# AD_i2C_SPI.net
KiCad netlist of a schematic drawn in Altium Designer
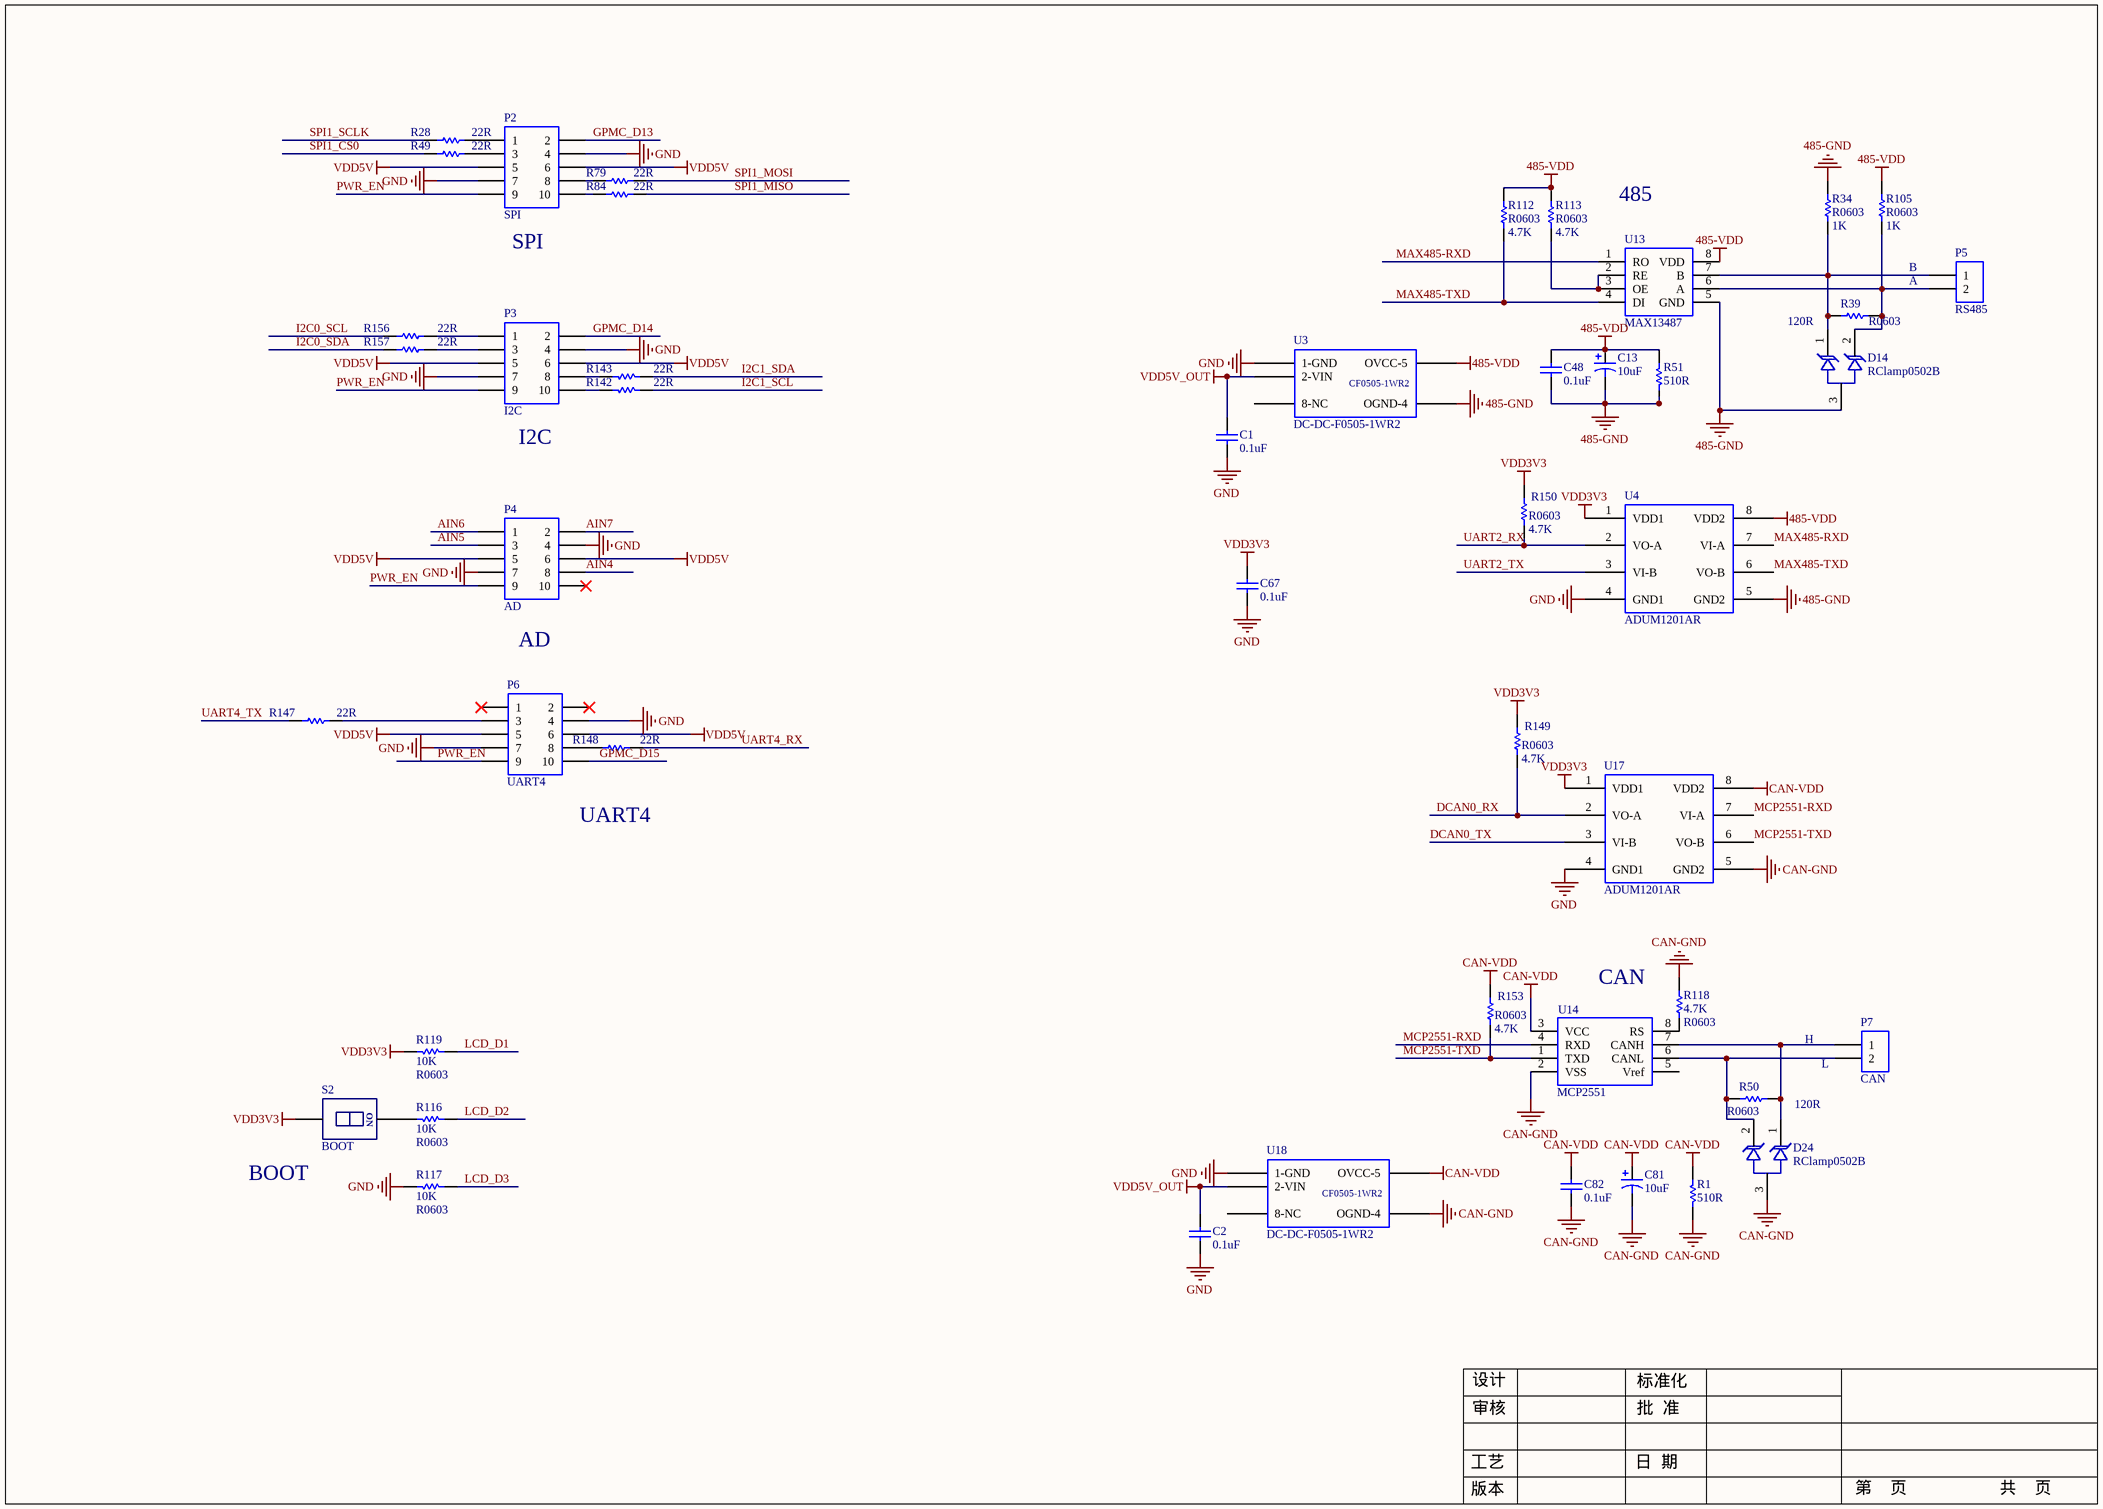
[diagram p0: AD & i2C & SPI.SchDoc]

(export (version "E")
  (design (tool "Eeschema 10.0.6"))
  (components
    (comp (ref "C1")
      (value "0.1uF")
      (description "Capacitor")
      (fields (field (name "Comment") "C0603") (field (name "PUBLISHER") "Altium Limited"))
      (libsource (lib "OK335xD") (part "Cap"))
    )
    (comp (ref "C2")
      (value "0.1uF")
      (description "Capacitor")
      (fields (field (name "Comment") "C0603") (field (name "PUBLISHER") "Altium Limited"))
      (libsource (lib "OK335xD") (part "Cap"))
    )
    (comp (ref "C13")
      (value "10uF")
      (footprint "TC3216A")
      (description "Polarized Capacitor (Surface Mount)")
      (fields (field (name "Comment") "Cap Pol3") (field (name "PUBLISHER") "Altium Limited"))
      (libsource (lib "OK335xD") (part "Cap Pol3"))
    )
    (comp (ref "C48")
      (value "0.1uF")
      (description "Capacitor")
      (fields (field (name "Comment") "C0603") (field (name "PUBLISHER") "Altium Limited"))
      (libsource (lib "OK335xD") (part "Cap"))
    )
    (comp (ref "C67")
      (value "0.1uF")
      (description "Capacitor")
      (fields (field (name "Comment") "C0603") (field (name "PUBLISHER") "Altium Limited"))
      (libsource (lib "OK335xD") (part "Cap"))
    )
    (comp (ref "C81")
      (value "10uF")
      (footprint "TC3216A")
      (description "Polarized Capacitor (Surface Mount)")
      (fields (field (name "Comment") "Cap Pol3") (field (name "PUBLISHER") "Altium Limited"))
      (libsource (lib "OK335xD") (part "Cap Pol3"))
    )
    (comp (ref "C82")
      (value "0.1uF")
      (description "Capacitor")
      (fields (field (name "Comment") "C0603") (field (name "PUBLISHER") "Altium Limited"))
      (libsource (lib "OK335xD") (part "Cap"))
    )
    (comp (ref "D14")
      (value "RClamp0502B")
      (footprint "SOT-523")
      (fields (field (name "Comment") "LCTVS"))
      (libsource (lib "Sch") (part "LCTVS"))
    )
    (comp (ref "D24")
      (value "RClamp0502B")
      (footprint "SOT-523")
      (fields (field (name "Comment") "LCTVS"))
      (libsource (lib "Sch") (part "LCTVS"))
    )
    (comp (ref "P2")
      (value "SPI")
      (footprint "IDC10S")
      (description "Header, 5-Pin, Dual row")
      (fields (field (name "PUBLISHER") "Altium Limited"))
      (libsource (lib "OK335xD") (part "Header 5X2"))
    )
    (comp (ref "P3")
      (value "I2C")
      (footprint "IDC10S")
      (description "Header, 5-Pin, Dual row")
      (fields (field (name "PUBLISHER") "Altium Limited"))
      (libsource (lib "OK335xD") (part "Header 5X2"))
    )
    (comp (ref "P4")
      (value "AD")
      (footprint "IDC10S")
      (description "Header, 5-Pin, Dual row")
      (fields (field (name "PUBLISHER") "Altium Limited"))
      (libsource (lib "OK335xD") (part "Header 5X2"))
    )
    (comp (ref "P5")
      (value "RS485")
      (footprint "2EDGKA-5.08-2P")
      (description "Header, 2-Pin")
      (fields (field (name "PUBLISHER") "Altium Limited"))
      (libsource (lib "OK335xD") (part "Header 2"))
    )
    (comp (ref "P6")
      (value "UART4")
      (footprint "IDC10S")
      (description "Header, 5-Pin, Dual row")
      (fields (field (name "PUBLISHER") "Altium Limited"))
      (libsource (lib "OK335xD") (part "Header 5X2"))
    )
    (comp (ref "P7")
      (value "CAN")
      (footprint "2EDGKA-5.08-2P")
      (description "Header, 2-Pin")
      (fields (field (name "PUBLISHER") "Altium Limited"))
      (libsource (lib "OK335xD") (part "Header 2"))
    )
    (comp (ref "R1")
      (value "510R")
      (footprint "1206")
      (description "Resistor")
      (fields (field (name "Comment") "R1808") (field (name "PUBLISHER") "Altium Limited"))
      (libsource (lib "Miscellaneous Devices") (part "Res1"))
    )
    (comp (ref "R28")
      (value "22R")
      (footprint "OK335xD_V1.0:R0603_M1608")
      (description "Resistor")
      (fields (field (name "Comment") "R0603") (field (name "PUBLISHER") "Altium Limited"))
      (libsource (lib "Miscellaneous Devices") (part "Res1"))
    )
    (comp (ref "R34")
      (value "R0603")
      (footprint "OK335xD_V1.0:R0603_M1608")
      (description "Resistor")
      (fields (field (name "ALTIUM_VALUE") "1K") (field (name "PUBLISHER") "Altium Limited"))
      (libsource (lib "Miscellaneous Devices") (part "Res1"))
    )
    (comp (ref "R39")
      (value "R0603")
      (footprint "OK335xD_V1.0:R0603_M1608")
      (description "Resistor")
      (fields (field (name "ALTIUM_VALUE") "120R") (field (name "PUBLISHER") "Altium Limited"))
      (libsource (lib "Miscellaneous Devices") (part "Res1"))
    )
    (comp (ref "R49")
      (value "22R")
      (footprint "OK335xD_V1.0:R0603_M1608")
      (description "Resistor")
      (fields (field (name "Comment") "R0603") (field (name "PUBLISHER") "Altium Limited"))
      (libsource (lib "Miscellaneous Devices") (part "Res1"))
    )
    (comp (ref "R50")
      (value "R0603")
      (footprint "OK335xD_V1.0:R0603_M1608")
      (description "Resistor")
      (fields (field (name "ALTIUM_VALUE") "120R") (field (name "PUBLISHER") "Altium Limited"))
      (libsource (lib "Miscellaneous Devices") (part "Res1"))
    )
    (comp (ref "R51")
      (value "510R")
      (footprint "1206")
      (description "Resistor")
      (fields (field (name "Comment") "R1808") (field (name "PUBLISHER") "Altium Limited"))
      (libsource (lib "Miscellaneous Devices") (part "Res1"))
    )
    (comp (ref "R79")
      (value "22R")
      (footprint "OK335xD_V1.0:R0603_M1608")
      (description "Resistor")
      (fields (field (name "Comment") "R0603") (field (name "PUBLISHER") "Altium Limited"))
      (libsource (lib "Miscellaneous Devices") (part "Res1"))
    )
    (comp (ref "R84")
      (value "22R")
      (footprint "OK335xD_V1.0:R0603_M1608")
      (description "Resistor")
      (fields (field (name "Comment") "R0603") (field (name "PUBLISHER") "Altium Limited"))
      (libsource (lib "Miscellaneous Devices") (part "Res1"))
    )
    (comp (ref "R105")
      (value "R0603")
      (footprint "OK335xD_V1.0:R0603_M1608")
      (description "Resistor")
      (fields (field (name "ALTIUM_VALUE") "1K") (field (name "PUBLISHER") "Altium Limited"))
      (libsource (lib "Miscellaneous Devices") (part "Res1"))
    )
    (comp (ref "R112")
      (value "R0603")
      (footprint "OK335xD_V1.0:R0603_M1608")
      (description "Resistor")
      (fields (field (name "ALTIUM_VALUE") "4.7K") (field (name "PUBLISHER") "Altium Limited"))
      (libsource (lib "Miscellaneous Devices") (part "Res1"))
    )
    (comp (ref "R113")
      (value "R0603")
      (footprint "OK335xD_V1.0:R0603_M1608")
      (description "Resistor")
      (fields (field (name "ALTIUM_VALUE") "4.7K") (field (name "PUBLISHER") "Altium Limited"))
      (libsource (lib "Miscellaneous Devices") (part "Res1"))
    )
    (comp (ref "R116")
      (value "10K")
      (footprint "R0603_M1608")
      (description "R0603")
      (fields (field (name "ALTIUM_VALUE") "R0603") (field (name "PUBLISHER") "Altium Limited"))
      (libsource (lib "Miscellaneous Devices") (part "Res1"))
    )
    (comp (ref "R117")
      (value "10K")
      (footprint "R0603_M1608")
      (description "R0603")
      (fields (field (name "ALTIUM_VALUE") "R0603") (field (name "PUBLISHER") "Altium Limited"))
      (libsource (lib "Miscellaneous Devices") (part "Res1"))
    )
    (comp (ref "R118")
      (value "4.7K")
      (footprint "R0603_M1608")
      (description "R0603")
      (fields (field (name "ALTIUM_VALUE") "R0603") (field (name "PUBLISHER") "Altium Limited"))
      (libsource (lib "Miscellaneous Devices") (part "Res1"))
    )
    (comp (ref "R119")
      (value "10K")
      (footprint "R0603_M1608")
      (description "R0603")
      (fields (field (name "ALTIUM_VALUE") "R0603") (field (name "PUBLISHER") "Altium Limited"))
      (libsource (lib "Miscellaneous Devices") (part "Res1"))
    )
    (comp (ref "R142")
      (value "22R")
      (footprint "OK335xD_V1.0:R0603_M1608")
      (description "Resistor")
      (fields (field (name "Comment") "R0603") (field (name "PUBLISHER") "Altium Limited"))
      (libsource (lib "Miscellaneous Devices") (part "Res1"))
    )
    (comp (ref "R143")
      (value "22R")
      (footprint "OK335xD_V1.0:R0603_M1608")
      (description "Resistor")
      (fields (field (name "Comment") "R0603") (field (name "PUBLISHER") "Altium Limited"))
      (libsource (lib "Miscellaneous Devices") (part "Res1"))
    )
    (comp (ref "R147")
      (value "22R")
      (footprint "OK335xD_V1.0:R0603_M1608")
      (description "Resistor")
      (fields (field (name "Comment") "R0603") (field (name "PUBLISHER") "Altium Limited"))
      (libsource (lib "Miscellaneous Devices") (part "Res1"))
    )
    (comp (ref "R148")
      (value "22R")
      (footprint "OK335xD_V1.0:R0603_M1608")
      (description "Resistor")
      (fields (field (name "Comment") "R0603") (field (name "PUBLISHER") "Altium Limited"))
      (libsource (lib "Miscellaneous Devices") (part "Res1"))
    )
    (comp (ref "R149")
      (value "R0603")
      (footprint "OK335xD_V1.0:R0603_M1608")
      (description "Resistor")
      (fields (field (name "ALTIUM_VALUE") "4.7K") (field (name "PUBLISHER") "Altium Limited"))
      (libsource (lib "Miscellaneous Devices") (part "Res1"))
    )
    (comp (ref "R150")
      (value "R0603")
      (footprint "OK335xD_V1.0:R0603_M1608")
      (description "Resistor")
      (fields (field (name "ALTIUM_VALUE") "4.7K") (field (name "PUBLISHER") "Altium Limited"))
      (libsource (lib "Miscellaneous Devices") (part "Res1"))
    )
    (comp (ref "R153")
      (value "R0603")
      (footprint "OK335xD_V1.0:R0603_M1608")
      (description "Resistor")
      (fields (field (name "ALTIUM_VALUE") "4.7K") (field (name "PUBLISHER") "Altium Limited"))
      (libsource (lib "Miscellaneous Devices") (part "Res1"))
    )
    (comp (ref "R156")
      (value "22R")
      (footprint "OK335xD_V1.0:R0603_M1608")
      (description "Resistor")
      (fields (field (name "Comment") "R0603") (field (name "PUBLISHER") "Altium Limited"))
      (libsource (lib "Miscellaneous Devices") (part "Res1"))
    )
    (comp (ref "R157")
      (value "22R")
      (footprint "OK335xD_V1.0:R0603_M1608")
      (description "Resistor")
      (fields (field (name "Comment") "R0603") (field (name "PUBLISHER") "Altium Limited"))
      (libsource (lib "Miscellaneous Devices") (part "Res1"))
    )
    (comp (ref "S2")
      (value "BOOT")
      (footprint "SWITCH_1P")
      (libsource (lib "Miscellaneous Connectors") (part "SW DIP-1"))
    )
    (comp (ref "U3")
      (value "DC-DC-F0505-1WR2")
      (footprint "CF0505-1WR2")
      (libsource (lib "OK335xD") (part "DC-DC-F0505-1WR2"))
    )
    (comp (ref "U4")
      (value "ADUM1201AR")
      (footprint "SO8_N - ADUM1201")
      (libsource (lib "OK335xD") (part "ADuM1201"))
    )
    (comp (ref "U13")
      (value "MAX13487")
      (footprint "SOIC-8N")
      (description "SOIC8")
      (libsource (lib "OK335xD") (part "MAX485"))
    )
    (comp (ref "U14")
      (value "MCP2551")
      (footprint "SOIC-8N")
      (description "SOIC8")
      (libsource (lib "OK335xD") (part "MCP2551"))
    )
    (comp (ref "U17")
      (value "ADUM1201AR")
      (footprint "SO8_N - ADUM1201")
      (libsource (lib "OK335xD") (part "ADuM1201"))
    )
    (comp (ref "U18")
      (value "DC-DC-F0505-1WR2")
      (footprint "CF0505-1WR2")
      (libsource (lib "OK335xD") (part "DC-DC-F0505-1WR2"))
    )
  )
  (nets
    (net (code "1") (name "/AIN4") (class "Default")
      (node (ref "P4") (pin "8") (pinfunction "8_8") (pintype "passive"))
    )
    (net (code "2") (name "/AIN5") (class "Default")
      (node (ref "P4") (pin "3") (pinfunction "3_3") (pintype "passive"))
    )
    (net (code "3") (name "/AIN6") (class "Default")
      (node (ref "P4") (pin "1") (pinfunction "1_1") (pintype "passive"))
    )
    (net (code "4") (name "/AIN7") (class "Default")
      (node (ref "P4") (pin "2") (pinfunction "2_2") (pintype "passive"))
    )
    (net (code "5") (name "/DCAN0_RX") (class "Default")
      (node (ref "R149") (pin "2") (pinfunction "2_2") (pintype "passive"))
      (node (ref "U17") (pin "2") (pinfunction "VO-A_2") (pintype "passive"))
    )
    (net (code "6") (name "/DCAN0_TX") (class "Default")
      (node (ref "U17") (pin "3") (pinfunction "VI-B_3") (pintype "passive"))
    )
    (net (code "7") (name "/GPMC_D13") (class "Default")
      (node (ref "P2") (pin "2") (pinfunction "2_2") (pintype "passive"))
    )
    (net (code "8") (name "/GPMC_D14") (class "Default")
      (node (ref "P3") (pin "2") (pinfunction "2_2") (pintype "passive"))
    )
    (net (code "9") (name "/GPMC_D15") (class "Default")
      (node (ref "P6") (pin "10") (pinfunction "10_10") (pintype "passive"))
    )
    (net (code "10") (name "/I2C0_SCL") (class "Default")
      (node (ref "R156") (pin "2") (pinfunction "2_2") (pintype "passive"))
    )
    (net (code "11") (name "/I2C0_SDA") (class "Default")
      (node (ref "R157") (pin "2") (pinfunction "2_2") (pintype "passive"))
    )
    (net (code "12") (name "/I2C1_SCL") (class "Default")
      (node (ref "R142") (pin "1") (pinfunction "1_1") (pintype "passive"))
    )
    (net (code "13") (name "/I2C1_SDA") (class "Default")
      (node (ref "R143") (pin "1") (pinfunction "1_1") (pintype "passive"))
    )
    (net (code "14") (name "/LCD_D1") (class "Default")
      (node (ref "R119") (pin "1") (pinfunction "1_1") (pintype "passive"))
    )
    (net (code "15") (name "/LCD_D2") (class "Default")
      (node (ref "R116") (pin "1") (pinfunction "1_1") (pintype "passive"))
    )
    (net (code "16") (name "/LCD_D3") (class "Default")
      (node (ref "R117") (pin "1") (pinfunction "1_1") (pintype "passive"))
    )
    (net (code "17") (name "/MAX485-RXD") (class "Default")
      (node (ref "U13") (pin "1") (pinfunction "RO_1") (pintype "passive"))
      (node (ref "U4") (pin "7") (pinfunction "VI-A_7") (pintype "passive"))
    )
    (net (code "18") (name "/MAX485-TXD") (class "Default")
      (node (ref "R112") (pin "2") (pinfunction "2_2") (pintype "passive"))
      (node (ref "U13") (pin "4") (pinfunction "DI_4") (pintype "passive"))
      (node (ref "U4") (pin "6") (pinfunction "VO-B_6") (pintype "passive"))
    )
    (net (code "19") (name "/MCP2551-RXD") (class "Default")
      (node (ref "U14") (pin "4") (pinfunction "RXD_4") (pintype "passive"))
      (node (ref "U17") (pin "7") (pinfunction "VI-A_7") (pintype "passive"))
    )
    (net (code "20") (name "/MCP2551-TXD") (class "Default")
      (node (ref "R153") (pin "2") (pinfunction "2_2") (pintype "passive"))
      (node (ref "U14") (pin "1") (pinfunction "TXD_1") (pintype "passive"))
      (node (ref "U17") (pin "6") (pinfunction "VO-B_6") (pintype "passive"))
    )
    (net (code "21") (name "/PWR_EN") (class "Default")
      (node (ref "P2") (pin "9") (pinfunction "9_9") (pintype "passive"))
      (node (ref "P3") (pin "9") (pinfunction "9_9") (pintype "passive"))
      (node (ref "P4") (pin "9") (pinfunction "9_9") (pintype "passive"))
      (node (ref "P6") (pin "9") (pinfunction "9_9") (pintype "passive"))
    )
    (net (code "22") (name "/SPI1_CS0") (class "Default")
      (node (ref "R49") (pin "2") (pinfunction "2_2") (pintype "passive"))
    )
    (net (code "23") (name "/SPI1_MISO") (class "Default")
      (node (ref "R84") (pin "1") (pinfunction "1_1") (pintype "passive"))
    )
    (net (code "24") (name "/SPI1_MOSI") (class "Default")
      (node (ref "R79") (pin "1") (pinfunction "1_1") (pintype "passive"))
    )
    (net (code "25") (name "/SPI1_SCLK") (class "Default")
      (node (ref "R28") (pin "2") (pinfunction "2_2") (pintype "passive"))
    )
    (net (code "26") (name "/UART2_RX") (class "Default")
      (node (ref "R150") (pin "2") (pinfunction "2_2") (pintype "passive"))
      (node (ref "U4") (pin "2") (pinfunction "VO-A_2") (pintype "passive"))
    )
    (net (code "27") (name "/UART2_TX") (class "Default")
      (node (ref "U4") (pin "3") (pinfunction "VI-B_3") (pintype "passive"))
    )
    (net (code "28") (name "/UART4_RX") (class "Default")
      (node (ref "R148") (pin "2") (pinfunction "2_2") (pintype "passive"))
    )
    (net (code "29") (name "/UART4_TX") (class "Default")
      (node (ref "R147") (pin "1") (pinfunction "1_1") (pintype "passive"))
    )
    (net (code "30") (name "485-GND") (class "Default")
      (node (ref "C13") (pin "2") (pinfunction "2_2") (pintype "passive"))
      (node (ref "C48") (pin "1") (pinfunction "1_1") (pintype "passive"))
      (node (ref "D14") (pin "3") (pintype "passive"))
      (node (ref "R34") (pin "1") (pinfunction "1_1") (pintype "passive"))
      (node (ref "R51") (pin "2") (pinfunction "2_2") (pintype "passive"))
      (node (ref "U13") (pin "5") (pinfunction "GND_5") (pintype "passive"))
      (node (ref "U3") (pin "4") (pinfunction "OGND-4_4") (pintype "passive"))
      (node (ref "U4") (pin "5") (pinfunction "GND2_5") (pintype "passive"))
    )
    (net (code "31") (name "485-VDD") (class "Default")
      (node (ref "C13") (pin "1") (pinfunction "1_1") (pintype "passive"))
      (node (ref "C48") (pin "2") (pinfunction "2_2") (pintype "passive"))
      (node (ref "R105") (pin "1") (pinfunction "1_1") (pintype "passive"))
      (node (ref "R112") (pin "1") (pinfunction "1_1") (pintype "passive"))
      (node (ref "R113") (pin "1") (pinfunction "1_1") (pintype "passive"))
      (node (ref "R51") (pin "1") (pinfunction "1_1") (pintype "passive"))
      (node (ref "U13") (pin "8") (pinfunction "VDD_8") (pintype "passive"))
      (node (ref "U3") (pin "5") (pinfunction "OVCC-5_5") (pintype "passive"))
      (node (ref "U4") (pin "8") (pinfunction "VDD2_8") (pintype "passive"))
    )
    (net (code "32") (name "CAN-GND") (class "Default")
      (node (ref "C81") (pin "2") (pinfunction "2_2") (pintype "passive"))
      (node (ref "C82") (pin "1") (pinfunction "1_1") (pintype "passive"))
      (node (ref "D24") (pin "3") (pintype "passive"))
      (node (ref "R1") (pin "2") (pinfunction "2_2") (pintype "passive"))
      (node (ref "R118") (pin "1") (pinfunction "1_1") (pintype "passive"))
      (node (ref "U14") (pin "2") (pinfunction "VSS_2") (pintype "passive"))
      (node (ref "U17") (pin "5") (pinfunction "GND2_5") (pintype "passive"))
      (node (ref "U18") (pin "4") (pinfunction "OGND-4_4") (pintype "passive"))
    )
    (net (code "33") (name "CAN-VDD") (class "Default")
      (node (ref "C81") (pin "1") (pinfunction "1_1") (pintype "passive"))
      (node (ref "C82") (pin "2") (pinfunction "2_2") (pintype "passive"))
      (node (ref "R1") (pin "1") (pinfunction "1_1") (pintype "passive"))
      (node (ref "R153") (pin "1") (pinfunction "1_1") (pintype "passive"))
      (node (ref "U14") (pin "3") (pinfunction "VCC_3") (pintype "passive"))
      (node (ref "U17") (pin "8") (pinfunction "VDD2_8") (pintype "passive"))
      (node (ref "U18") (pin "5") (pinfunction "OVCC-5_5") (pintype "passive"))
    )
    (net (code "34") (name "GND") (class "Default")
      (node (ref "C1") (pin "1") (pinfunction "1_1") (pintype "passive"))
      (node (ref "C2") (pin "1") (pinfunction "1_1") (pintype "passive"))
      (node (ref "C67") (pin "1") (pinfunction "1_1") (pintype "passive"))
      (node (ref "P2") (pin "4") (pinfunction "4_4") (pintype "passive"))
      (node (ref "P2") (pin "7") (pinfunction "7_7") (pintype "passive"))
      (node (ref "P3") (pin "4") (pinfunction "4_4") (pintype "passive"))
      (node (ref "P3") (pin "7") (pinfunction "7_7") (pintype "passive"))
      (node (ref "P4") (pin "4") (pinfunction "4_4") (pintype "passive"))
      (node (ref "P4") (pin "7") (pinfunction "7_7") (pintype "passive"))
      (node (ref "P6") (pin "4") (pinfunction "4_4") (pintype "passive"))
      (node (ref "P6") (pin "7") (pinfunction "7_7") (pintype "passive"))
      (node (ref "R117") (pin "2") (pinfunction "2_2") (pintype "passive"))
      (node (ref "U17") (pin "4") (pinfunction "GND1_4") (pintype "passive"))
      (node (ref "U18") (pin "1") (pinfunction "1-GND_1") (pintype "passive"))
      (node (ref "U3") (pin "1") (pinfunction "1-GND_1") (pintype "passive"))
      (node (ref "U4") (pin "4") (pinfunction "GND1_4") (pintype "passive"))
    )
    (net (code "35") (name "Net-(P2-Pad1)") (class "Default")
      (node (ref "P2") (pin "1") (pinfunction "1_1") (pintype "passive"))
      (node (ref "R28") (pin "1") (pinfunction "1_1") (pintype "passive"))
    )
    (net (code "36") (name "Net-(P2-Pad3)") (class "Default")
      (node (ref "P2") (pin "3") (pinfunction "3_3") (pintype "passive"))
      (node (ref "R49") (pin "1") (pinfunction "1_1") (pintype "passive"))
    )
    (net (code "37") (name "Net-(P2-Pad8)") (class "Default")
      (node (ref "P2") (pin "8") (pinfunction "8_8") (pintype "passive"))
      (node (ref "R79") (pin "2") (pinfunction "2_2") (pintype "passive"))
    )
    (net (code "38") (name "Net-(P2-Pad10)") (class "Default")
      (node (ref "P2") (pin "10") (pinfunction "10_10") (pintype "passive"))
      (node (ref "R84") (pin "2") (pinfunction "2_2") (pintype "passive"))
    )
    (net (code "39") (name "Net-(P3-Pad1)") (class "Default")
      (node (ref "P3") (pin "1") (pinfunction "1_1") (pintype "passive"))
      (node (ref "R156") (pin "1") (pinfunction "1_1") (pintype "passive"))
    )
    (net (code "40") (name "Net-(P3-Pad3)") (class "Default")
      (node (ref "P3") (pin "3") (pinfunction "3_3") (pintype "passive"))
      (node (ref "R157") (pin "1") (pinfunction "1_1") (pintype "passive"))
    )
    (net (code "41") (name "Net-(P3-Pad8)") (class "Default")
      (node (ref "P3") (pin "8") (pinfunction "8_8") (pintype "passive"))
      (node (ref "R143") (pin "2") (pinfunction "2_2") (pintype "passive"))
    )
    (net (code "42") (name "Net-(P3-Pad10)") (class "Default")
      (node (ref "P3") (pin "10") (pinfunction "10_10") (pintype "passive"))
      (node (ref "R142") (pin "2") (pinfunction "2_2") (pintype "passive"))
    )
    (net (code "43") (name "Net-(P6-Pad3)") (class "Default")
      (node (ref "P6") (pin "3") (pinfunction "3_3") (pintype "passive"))
      (node (ref "R147") (pin "2") (pinfunction "2_2") (pintype "passive"))
    )
    (net (code "44") (name "Net-(P6-Pad8)") (class "Default")
      (node (ref "P6") (pin "8") (pinfunction "8_8") (pintype "passive"))
      (node (ref "R148") (pin "1") (pinfunction "1_1") (pintype "passive"))
    )
    (net (code "45") (name "Net-(R116-Pad2)") (class "Default")
      (node (ref "R116") (pin "2") (pinfunction "2_2") (pintype "passive"))
      (node (ref "S2") (pin "2") (pinfunction "2_2") (pintype "passive"))
    )
    (net (code "46") (name "Net-(U13-A)") (class "Default")
      (node (ref "D14") (pin "2") (pinfunction "2_2") (pintype "passive"))
      (node (ref "P5") (pin "2") (pinfunction "2_2") (pintype "passive"))
      (node (ref "R105") (pin "2") (pinfunction "2_2") (pintype "passive"))
      (node (ref "R39") (pin "1") (pinfunction "1_1") (pintype "passive"))
      (node (ref "U13") (pin "6") (pinfunction "A_6") (pintype "passive"))
    )
    (net (code "47") (name "Net-(U13-B)") (class "Default")
      (node (ref "D14") (pin "1") (pinfunction "1_1") (pintype "passive"))
      (node (ref "P5") (pin "1") (pinfunction "1_1") (pintype "passive"))
      (node (ref "R34") (pin "2") (pinfunction "2_2") (pintype "passive"))
      (node (ref "R39") (pin "2") (pinfunction "2_2") (pintype "passive"))
      (node (ref "U13") (pin "7") (pinfunction "B_7") (pintype "passive"))
    )
    (net (code "48") (name "Net-(U13-OE)") (class "Default")
      (node (ref "R113") (pin "2") (pinfunction "2_2") (pintype "passive"))
      (node (ref "U13") (pin "2") (pinfunction "RE_2") (pintype "passive"))
      (node (ref "U13") (pin "3") (pinfunction "OE_3") (pintype "passive"))
    )
    (net (code "49") (name "Net-(U14-CANH)") (class "Default")
      (node (ref "D24") (pin "1") (pinfunction "1_1") (pintype "passive"))
      (node (ref "P7") (pin "1") (pinfunction "1_1") (pintype "passive"))
      (node (ref "R50") (pin "1") (pinfunction "1_1") (pintype "passive"))
      (node (ref "U14") (pin "7") (pinfunction "CANH_7") (pintype "passive"))
    )
    (net (code "50") (name "Net-(U14-CANL)") (class "Default")
      (node (ref "D24") (pin "2") (pinfunction "2_2") (pintype "passive"))
      (node (ref "P7") (pin "2") (pinfunction "2_2") (pintype "passive"))
      (node (ref "R50") (pin "2") (pinfunction "2_2") (pintype "passive"))
      (node (ref "U14") (pin "6") (pinfunction "CANL_6") (pintype "passive"))
    )
    (net (code "51") (name "Net-(U14-RS)") (class "Default")
      (node (ref "R118") (pin "2") (pinfunction "2_2") (pintype "passive"))
      (node (ref "U14") (pin "8") (pinfunction "RS_8") (pintype "passive"))
    )
    (net (code "52") (name "VDD3V3") (class "Default")
      (node (ref "C67") (pin "2") (pinfunction "2_2") (pintype "passive"))
      (node (ref "R119") (pin "2") (pinfunction "2_2") (pintype "passive"))
      (node (ref "R149") (pin "1") (pinfunction "1_1") (pintype "passive"))
      (node (ref "R150") (pin "1") (pinfunction "1_1") (pintype "passive"))
      (node (ref "S2") (pin "1") (pinfunction "1_1") (pintype "passive"))
      (node (ref "U17") (pin "1") (pinfunction "VDD1_1") (pintype "passive"))
      (node (ref "U4") (pin "1") (pinfunction "VDD1_1") (pintype "passive"))
    )
    (net (code "53") (name "VDD5V") (class "Default")
      (node (ref "P2") (pin "5") (pinfunction "5_5") (pintype "passive"))
      (node (ref "P2") (pin "6") (pinfunction "6_6") (pintype "passive"))
      (node (ref "P3") (pin "5") (pinfunction "5_5") (pintype "passive"))
      (node (ref "P3") (pin "6") (pinfunction "6_6") (pintype "passive"))
      (node (ref "P4") (pin "5") (pinfunction "5_5") (pintype "passive"))
      (node (ref "P4") (pin "6") (pinfunction "6_6") (pintype "passive"))
      (node (ref "P6") (pin "5") (pinfunction "5_5") (pintype "passive"))
      (node (ref "P6") (pin "6") (pinfunction "6_6") (pintype "passive"))
    )
    (net (code "54") (name "VDD5V_OUT") (class "Default")
      (node (ref "C1") (pin "2") (pinfunction "2_2") (pintype "passive"))
      (node (ref "C2") (pin "2") (pinfunction "2_2") (pintype "passive"))
      (node (ref "U18") (pin "2") (pinfunction "2-VIN_2") (pintype "passive"))
      (node (ref "U3") (pin "2") (pinfunction "2-VIN_2") (pintype "passive"))
    )
    (net (code "55") (name "unconnected-(P4-Pad10)") (class "Default")
      (node (ref "P4") (pin "10") (pinfunction "10_10") (pintype "passive+no_connect"))
    )
    (net (code "56") (name "unconnected-(P6-Pad1)") (class "Default")
      (node (ref "P6") (pin "1") (pinfunction "1_1") (pintype "passive+no_connect"))
    )
    (net (code "57") (name "unconnected-(P6-Pad2)") (class "Default")
      (node (ref "P6") (pin "2") (pinfunction "2_2") (pintype "passive+no_connect"))
    )
    (net (code "58") (name "unconnected-(U3-8-NC-Pad8)") (class "Default")
      (node (ref "U3") (pin "8") (pinfunction "8-NC_8") (pintype "passive"))
    )
    (net (code "59") (name "unconnected-(U14-Vref-Pad5)") (class "Default")
      (node (ref "U14") (pin "5") (pinfunction "Vref_5") (pintype "passive"))
    )
    (net (code "60") (name "unconnected-(U18-8-NC-Pad8)") (class "Default")
      (node (ref "U18") (pin "8") (pinfunction "8-NC_8") (pintype "passive"))
    )
  )
)
